# GATEWAY.net
KiCad netlist of a schematic drawn in Altium Designer
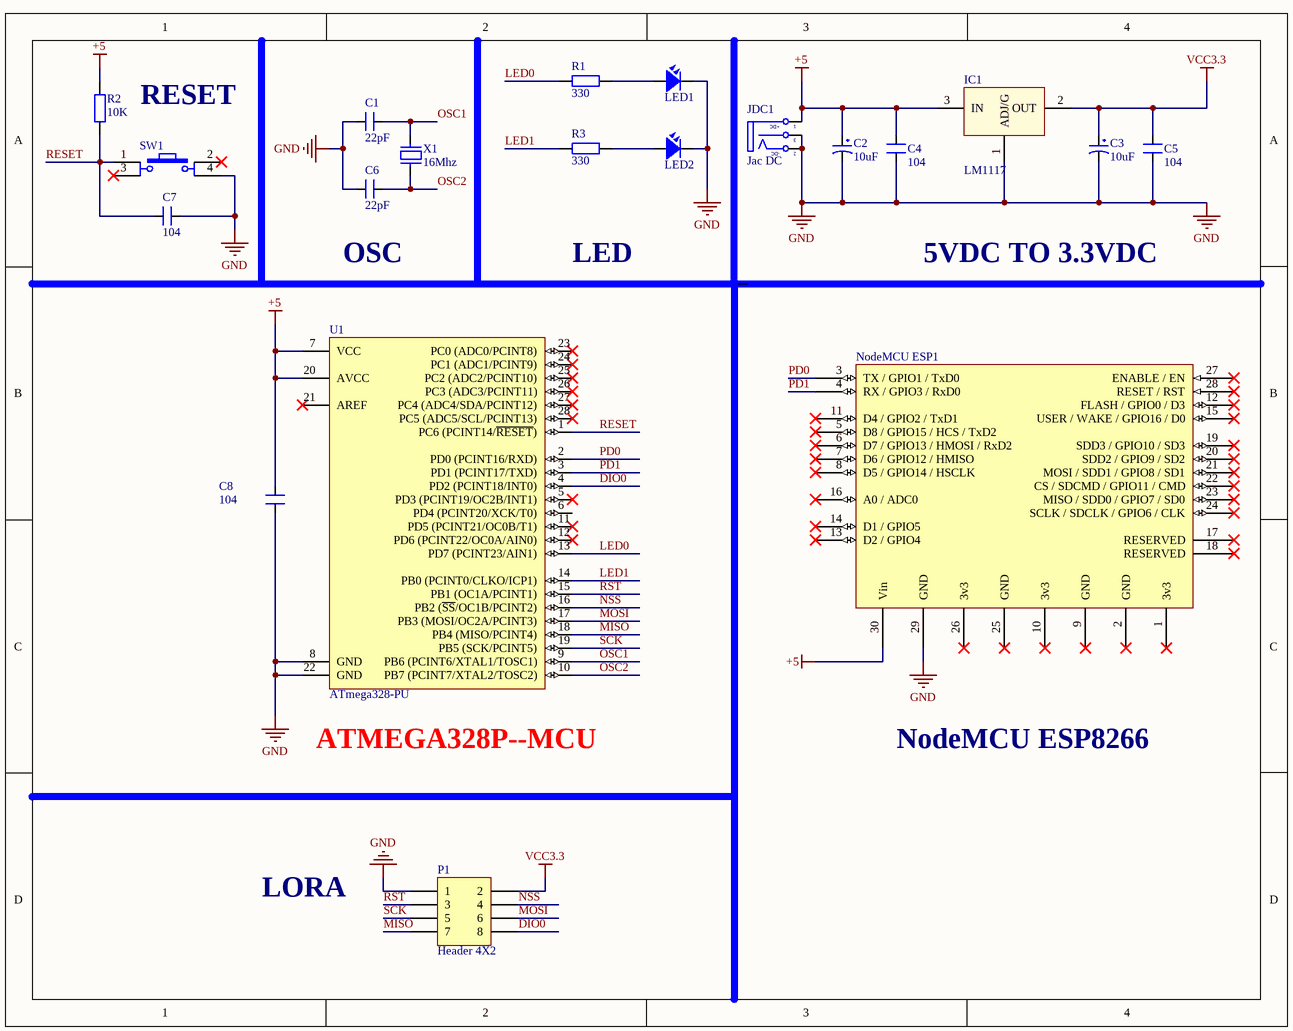
[diagram p0: GATEWAY.SchDoc]

(export (version "E")
  (design (tool "Eeschema 10.0.6"))
  (components
    (comp (ref "C1")
      (value "22pF")
      (footprint "CN1")
      (description "Cap np  1pF - 472pF")
      (libsource (lib "syhaunguyen") (part "CN1"))
    )
    (comp (ref "C2")
      (value "10uF")
      (footprint "CP1/2")
      (description "Cap P  0,1uF < 22uF , 16 - 50V")
      (libsource (lib "My Library") (part "CP1"))
    )
    (comp (ref "C3")
      (value "10uF")
      (footprint "CP1/2")
      (description "Cap P  0,1uF < 22uF , 16 - 50V")
      (libsource (lib "My Library") (part "CP1"))
    )
    (comp (ref "C4")
      (value "104")
      (footprint "CN2")
      (description "Cap np 104 => 105pF")
      (libsource (lib "syhaunguyen") (part "CN2"))
    )
    (comp (ref "C5")
      (value "104")
      (footprint "CN2")
      (description "Cap np 104 => 105pF")
      (libsource (lib "syhaunguyen") (part "CN2"))
    )
    (comp (ref "C6")
      (value "22pF")
      (footprint "CN1")
      (description "Cap np  1pF - 472pF")
      (libsource (lib "syhaunguyen") (part "CN1"))
    )
    (comp (ref "C7")
      (value "104")
      (footprint "CN2")
      (description "Cap np 104 => 105pF")
      (libsource (lib "syhaunguyen") (part "CN2"))
    )
    (comp (ref "C8")
      (value "104")
      (footprint "CN2")
      (description "Cap np 104 => 105pF")
      (libsource (lib "syhaunguyen") (part "CN2"))
    )
    (comp (ref "IC1")
      (value "LM1117")
      (footprint "SOT223-4N")
      (description "Available in 1.8V, 2.5V, 2.85V, 3.3V, 5V, and  Adjustable Versions")
      (libsource (lib "syhaunguyen") (part "LM1117"))
    )
    (comp (ref "JDC1")
      (value "Jac DC")
      (footprint "DC0")
      (description "Jac DC input")
      (libsource (lib "LIBRARY1") (part "DCIN"))
    )
    (comp (ref "LED1")
      (value "LED")
      (footprint "LED-5-Yellow")
      (description "LED Single colour Green and Red")
      (libsource (lib "syhaunguyen") (part "LED"))
    )
    (comp (ref "LED2")
      (value "LED")
      (footprint "LED-5-BLUE")
      (description "LED Single colour Green and Red")
      (libsource (lib "syhaunguyen") (part "LED"))
    )
    (comp (ref "NodeMCU ESP1")
      (value "NodeMCU")
      (footprint "NodeMCU DevKit v1.0 - Inside Labels")
      (libsource (lib "NodeMCU") (part "NodeMCU DevKit v1.0"))
    )
    (comp (ref "P1")
      (value "Header 4X2")
      (footprint "HDR2X4")
      (description "Header, 4-Pin, Dual row")
      (fields (field (name "PUBLISHER") "Altium Limited"))
      (libsource (lib "My Library") (part "Header 4X2"))
    )
    (comp (ref "R1")
      (value "330")
      (footprint "R1/2W")
      (description "Resistor 1/4W")
      (libsource (lib "syhaunguyen") (part "R1/4W"))
    )
    (comp (ref "R2")
      (value "10K")
      (footprint "R1/2W")
      (description "Resistor 1/4W")
      (libsource (lib "syhaunguyen") (part "R1/4W"))
    )
    (comp (ref "R3")
      (value "330")
      (footprint "R1/2W")
      (description "Resistor 1/4W")
      (libsource (lib "syhaunguyen") (part "R1/4W"))
    )
    (comp (ref "SW1")
      (value "SW")
      (footprint "SW4")
      (description "Switch button 4 pin")
      (libsource (lib "syhaunguyen") (part "SW4"))
    )
    (comp (ref "U1")
      (value "ATmega328-PU")
      (footprint "DIP28")
      (fields (field (name "PUBLISHER") "Altium Limited"))
      (libsource (lib "LIBRARY1") (part "ATmega328-PU"))
    )
    (comp (ref "X1")
      (value "16Mhz")
      (footprint "XT2")
      (description "Crystal For all Crystal 2pin.")
      (libsource (lib "hphonglib") (part "XT2"))
    )
  )
  (nets
    (net (code "1") (name "+5") (class "Default")
      (node (ref "C2") (pin "1") (pinfunction "1_1") (pintype "passive"))
      (node (ref "C4") (pin "2") (pinfunction "2_2") (pintype "passive"))
      (node (ref "C8") (pin "2") (pinfunction "2_2") (pintype "passive"))
      (node (ref "IC1") (pin "3") (pinfunction "IN_3") (pintype "passive"))
      (node (ref "JDC1") (pin "1") (pinfunction "T_1") (pintype "passive"))
      (node (ref "NodeMCU ESP1") (pin "30") (pinfunction "Vin_30") (pintype "passive"))
      (node (ref "R2") (pin "2") (pinfunction "2_2") (pintype "passive"))
      (node (ref "U1") (pin "20") (pinfunction "AVCC_20") (pintype "power_in"))
      (node (ref "U1") (pin "7") (pinfunction "VCC_7") (pintype "power_in"))
    )
    (net (code "2") (name "/DIO0") (class "Default")
      (node (ref "P1") (pin "8") (pinfunction "8_8") (pintype "passive"))
      (node (ref "U1") (pin "4") (pinfunction "PD2_(PCINT18/INT0)_4") (pintype "bidirectional"))
    )
    (net (code "3") (name "/LED0") (class "Default")
      (node (ref "R1") (pin "2") (pinfunction "2_2") (pintype "passive"))
      (node (ref "U1") (pin "13") (pinfunction "PD7_(PCINT23/AIN1)_13") (pintype "bidirectional"))
    )
    (net (code "4") (name "/LED1") (class "Default")
      (node (ref "R3") (pin "2") (pinfunction "2_2") (pintype "passive"))
      (node (ref "U1") (pin "14") (pinfunction "PB0_(PCINT0/CLKO/ICP1)_14") (pintype "bidirectional"))
    )
    (net (code "5") (name "/MISO") (class "Default")
      (node (ref "P1") (pin "7") (pinfunction "7_7") (pintype "passive"))
      (node (ref "U1") (pin "18") (pinfunction "PB4_(MISO/PCINT4)_18") (pintype "bidirectional"))
    )
    (net (code "6") (name "/MOSI") (class "Default")
      (node (ref "P1") (pin "6") (pinfunction "6_6") (pintype "passive"))
      (node (ref "U1") (pin "17") (pinfunction "PB3_(MOSI/OC2A/PCINT3)_17") (pintype "bidirectional"))
    )
    (net (code "7") (name "/NSS") (class "Default")
      (node (ref "P1") (pin "4") (pinfunction "4_4") (pintype "passive"))
      (node (ref "U1") (pin "16") (pinfunction "PB2_(~{SS}/OC1B/PCINT2)_16") (pintype "bidirectional"))
    )
    (net (code "8") (name "/OSC1") (class "Default")
      (node (ref "C1") (pin "2") (pinfunction "2_2") (pintype "passive"))
      (node (ref "U1") (pin "9") (pinfunction "PB6_(PCINT6/XTAL1/TOSC1)_9") (pintype "bidirectional"))
      (node (ref "X1") (pin "2") (pinfunction "2_2") (pintype "passive"))
    )
    (net (code "9") (name "/OSC2") (class "Default")
      (node (ref "C6") (pin "2") (pinfunction "2_2") (pintype "passive"))
      (node (ref "U1") (pin "10") (pinfunction "PB7_(PCINT7/XTAL2/TOSC2)_10") (pintype "bidirectional"))
      (node (ref "X1") (pin "1") (pinfunction "1_1") (pintype "passive"))
    )
    (net (code "10") (name "/PD0") (class "Default")
      (node (ref "NodeMCU ESP1") (pin "3") (pinfunction "TX_/_GPIO1_/_TxD0_3") (pintype "bidirectional"))
      (node (ref "U1") (pin "2") (pinfunction "PD0_(PCINT16/RXD)_2") (pintype "bidirectional"))
    )
    (net (code "11") (name "/PD1") (class "Default")
      (node (ref "NodeMCU ESP1") (pin "4") (pinfunction "RX_/_GPIO3_/_RxD0_4") (pintype "bidirectional"))
      (node (ref "U1") (pin "3") (pinfunction "PD1_(PCINT17/TXD)_3") (pintype "bidirectional"))
    )
    (net (code "12") (name "/RESET") (class "Default")
      (node (ref "C7") (pin "1") (pinfunction "1_1") (pintype "passive"))
      (node (ref "R2") (pin "1") (pinfunction "1_1") (pintype "passive"))
      (node (ref "SW1") (pin "1") (pintype "passive"))
      (node (ref "U1") (pin "1") (pinfunction "PC6_(PCINT14/~{RESET})_1") (pintype "bidirectional"))
    )
    (net (code "13") (name "/RST") (class "Default")
      (node (ref "P1") (pin "3") (pinfunction "3_3") (pintype "passive"))
      (node (ref "U1") (pin "15") (pinfunction "PB1_(OC1A/PCINT1)_15") (pintype "bidirectional"))
    )
    (net (code "14") (name "/SCK") (class "Default")
      (node (ref "P1") (pin "5") (pinfunction "5_5") (pintype "passive"))
      (node (ref "U1") (pin "19") (pinfunction "PB5_(SCK/PCINT5)_19") (pintype "bidirectional"))
    )
    (net (code "15") (name "GND") (class "Default")
      (node (ref "C1") (pin "1") (pinfunction "1_1") (pintype "passive"))
      (node (ref "C2") (pin "2") (pinfunction "2_2") (pintype "passive"))
      (node (ref "C3") (pin "2") (pinfunction "2_2") (pintype "passive"))
      (node (ref "C4") (pin "1") (pinfunction "1_1") (pintype "passive"))
      (node (ref "C5") (pin "1") (pinfunction "1_1") (pintype "passive"))
      (node (ref "C6") (pin "1") (pinfunction "1_1") (pintype "passive"))
      (node (ref "C7") (pin "2") (pinfunction "2_2") (pintype "passive"))
      (node (ref "C8") (pin "1") (pinfunction "1_1") (pintype "passive"))
      (node (ref "IC1") (pin "1") (pinfunction "ADJ/G_1") (pintype "passive"))
      (node (ref "JDC1") (pin "2") (pinfunction "TN_2") (pintype "passive"))
      (node (ref "JDC1") (pin "3") (pinfunction "S_3") (pintype "power_in"))
      (node (ref "LED1") (pin "2") (pinfunction "2_2") (pintype "passive"))
      (node (ref "LED2") (pin "2") (pinfunction "2_2") (pintype "passive"))
      (node (ref "NodeMCU ESP1") (pin "29") (pinfunction "GND_29") (pintype "passive"))
      (node (ref "P1") (pin "1") (pinfunction "1_1") (pintype "passive"))
      (node (ref "SW1") (pin "4") (pintype "passive"))
      (node (ref "U1") (pin "22") (pinfunction "GND_22") (pintype "power_in"))
      (node (ref "U1") (pin "8") (pinfunction "GND_8") (pintype "power_in"))
    )
    (net (code "16") (name "Net-(LED1-Pad1)") (class "Default")
      (node (ref "LED1") (pin "1") (pinfunction "1_1") (pintype "passive"))
      (node (ref "R1") (pin "1") (pinfunction "1_1") (pintype "passive"))
    )
    (net (code "17") (name "Net-(LED2-Pad1)") (class "Default")
      (node (ref "LED2") (pin "1") (pinfunction "1_1") (pintype "passive"))
      (node (ref "R3") (pin "1") (pinfunction "1_1") (pintype "passive"))
    )
    (net (code "18") (name "VCC3.3") (class "Default")
      (node (ref "C3") (pin "1") (pinfunction "1_1") (pintype "passive"))
      (node (ref "C5") (pin "2") (pinfunction "2_2") (pintype "passive"))
      (node (ref "IC1") (pin "2") (pinfunction "OUT_2") (pintype "passive"))
      (node (ref "P1") (pin "2") (pinfunction "2_2") (pintype "passive"))
    )
    (net (code "19") (name "unconnected-(NodeMCU ESP1-3v3-Pad1)") (class "Default")
      (node (ref "NodeMCU ESP1") (pin "1") (pinfunction "3v3_1") (pintype "power_in+no_connect"))
    )
    (net (code "20") (name "unconnected-(NodeMCU ESP1-3v3-Pad10)") (class "Default")
      (node (ref "NodeMCU ESP1") (pin "10") (pinfunction "3v3_10") (pintype "power_in+no_connect"))
    )
    (net (code "21") (name "unconnected-(NodeMCU ESP1-3v3-Pad26)") (class "Default")
      (node (ref "NodeMCU ESP1") (pin "26") (pinfunction "3v3_26") (pintype "power_in+no_connect"))
    )
    (net (code "22") (name "unconnected-(NodeMCU ESP1-A0_{slash}_ADC0-Pad16)") (class "Default")
      (node (ref "NodeMCU ESP1") (pin "16") (pinfunction "A0_/_ADC0_16") (pintype "bidirectional+no_connect"))
    )
    (net (code "23") (name "unconnected-(NodeMCU ESP1-CS_{slash}_SDCMD_{slash}_GPIO11_{slash}_CMD-Pad22)") (class "Default")
      (node (ref "NodeMCU ESP1") (pin "22") (pinfunction "CS_/_SDCMD_/_GPIO11_/_CMD_22") (pintype "bidirectional+no_connect"))
    )
    (net (code "24") (name "unconnected-(NodeMCU ESP1-D1_{slash}_GPIO5-Pad14)") (class "Default")
      (node (ref "NodeMCU ESP1") (pin "14") (pinfunction "D1_/_GPIO5_14") (pintype "bidirectional+no_connect"))
    )
    (net (code "25") (name "unconnected-(NodeMCU ESP1-D2_{slash}_GPIO4-Pad13)") (class "Default")
      (node (ref "NodeMCU ESP1") (pin "13") (pinfunction "D2_/_GPIO4_13") (pintype "bidirectional+no_connect"))
    )
    (net (code "26") (name "unconnected-(NodeMCU ESP1-D4_{slash}_GPIO2_{slash}_TxD1-Pad11)") (class "Default")
      (node (ref "NodeMCU ESP1") (pin "11") (pinfunction "D4_/_GPIO2_/_TxD1_11") (pintype "bidirectional+no_connect"))
    )
    (net (code "27") (name "unconnected-(NodeMCU ESP1-D5_{slash}_GPIO14_{slash}_HSCLK-Pad8)") (class "Default")
      (node (ref "NodeMCU ESP1") (pin "8") (pinfunction "D5_/_GPIO14_/_HSCLK_8") (pintype "bidirectional+no_connect"))
    )
    (net (code "28") (name "unconnected-(NodeMCU ESP1-D6_{slash}_GPIO12_{slash}_HMISO-Pad7)") (class "Default")
      (node (ref "NodeMCU ESP1") (pin "7") (pinfunction "D6_/_GPIO12_/_HMISO_7") (pintype "bidirectional+no_connect"))
    )
    (net (code "29") (name "unconnected-(NodeMCU ESP1-D7_{slash}_GPIO13_{slash}_HMOSI_{slash}_RxD2-Pad6)") (class "Default")
      (node (ref "NodeMCU ESP1") (pin "6") (pinfunction "D7_/_GPIO13_/_HMOSI_/_RxD2_6") (pintype "bidirectional+no_connect"))
    )
    (net (code "30") (name "unconnected-(NodeMCU ESP1-D8_{slash}_GPIO15_{slash}_HCS_{slash}_TxD2-Pad5)") (class "Default")
      (node (ref "NodeMCU ESP1") (pin "5") (pinfunction "D8_/_GPIO15_/_HCS_/_TxD2_5") (pintype "bidirectional+no_connect"))
    )
    (net (code "31") (name "unconnected-(NodeMCU ESP1-ENABLE_{slash}_EN-Pad27)") (class "Default")
      (node (ref "NodeMCU ESP1") (pin "27") (pinfunction "ENABLE_/_EN_27") (pintype "input+no_connect"))
    )
    (net (code "32") (name "unconnected-(NodeMCU ESP1-FLASH_{slash}_GPIO0_{slash}_D3-Pad12)") (class "Default")
      (node (ref "NodeMCU ESP1") (pin "12") (pinfunction "FLASH_/_GPIO0_/_D3_12") (pintype "bidirectional+no_connect"))
    )
    (net (code "33") (name "unconnected-(NodeMCU ESP1-GND-Pad2)") (class "Default")
      (node (ref "NodeMCU ESP1") (pin "2") (pinfunction "GND_2") (pintype "power_in+no_connect"))
    )
    (net (code "34") (name "unconnected-(NodeMCU ESP1-GND-Pad9)") (class "Default")
      (node (ref "NodeMCU ESP1") (pin "9") (pinfunction "GND_9") (pintype "power_in+no_connect"))
    )
    (net (code "35") (name "unconnected-(NodeMCU ESP1-GND-Pad25)") (class "Default")
      (node (ref "NodeMCU ESP1") (pin "25") (pinfunction "GND_25") (pintype "power_in+no_connect"))
    )
    (net (code "36") (name "unconnected-(NodeMCU ESP1-MISO_{slash}_SDD0_{slash}_GPIO7_{slash}_SD0-Pad23)") (class "Default")
      (node (ref "NodeMCU ESP1") (pin "23") (pinfunction "MISO_/_SDD0_/_GPIO7_/_SD0_23") (pintype "bidirectional+no_connect"))
    )
    (net (code "37") (name "unconnected-(NodeMCU ESP1-MOSI_{slash}_SDD1_{slash}_GPIO8_{slash}_SD1-Pad21)") (class "Default")
      (node (ref "NodeMCU ESP1") (pin "21") (pinfunction "MOSI_/_SDD1_/_GPIO8_/_SD1_21") (pintype "bidirectional+no_connect"))
    )
    (net (code "38") (name "unconnected-(NodeMCU ESP1-RESERVED-Pad17)") (class "Default")
      (node (ref "NodeMCU ESP1") (pin "17") (pinfunction "RESERVED_17") (pintype "passive+no_connect"))
    )
    (net (code "39") (name "unconnected-(NodeMCU ESP1-RESERVED-Pad18)") (class "Default")
      (node (ref "NodeMCU ESP1") (pin "18") (pinfunction "RESERVED_18") (pintype "passive+no_connect"))
    )
    (net (code "40") (name "unconnected-(NodeMCU ESP1-RESET_{slash}_RST-Pad28)") (class "Default")
      (node (ref "NodeMCU ESP1") (pin "28") (pinfunction "RESET_/_RST_28") (pintype "input+no_connect"))
    )
    (net (code "41") (name "unconnected-(NodeMCU ESP1-SCLK_{slash}_SDCLK_{slash}_GPIO6_{slash}_CLK-Pad24)") (class "Default")
      (node (ref "NodeMCU ESP1") (pin "24") (pinfunction "SCLK_/_SDCLK_/_GPIO6_/_CLK_24") (pintype "bidirectional+no_connect"))
    )
    (net (code "42") (name "unconnected-(NodeMCU ESP1-SDD2_{slash}_GPIO9_{slash}_SD2-Pad20)") (class "Default")
      (node (ref "NodeMCU ESP1") (pin "20") (pinfunction "SDD2_/_GPIO9_/_SD2_20") (pintype "bidirectional+no_connect"))
    )
    (net (code "43") (name "unconnected-(NodeMCU ESP1-SDD3_{slash}_GPIO10_{slash}_SD3-Pad19)") (class "Default")
      (node (ref "NodeMCU ESP1") (pin "19") (pinfunction "SDD3_/_GPIO10_/_SD3_19") (pintype "bidirectional+no_connect"))
    )
    (net (code "44") (name "unconnected-(NodeMCU ESP1-USER_{slash}_WAKE_{slash}_GPIO16_{slash}_D0-Pad15)") (class "Default")
      (node (ref "NodeMCU ESP1") (pin "15") (pinfunction "USER_/_WAKE_/_GPIO16_/_D0_15") (pintype "bidirectional+no_connect"))
    )
    (net (code "45") (name "unconnected-(SW1-Pad2)") (class "Default")
      (node (ref "SW1") (pin "2") (pintype "passive+no_connect"))
    )
    (net (code "46") (name "unconnected-(SW1-Pad3)") (class "Default")
      (node (ref "SW1") (pin "3") (pintype "passive+no_connect"))
    )
    (net (code "47") (name "unconnected-(U1-AREF-Pad21)") (class "Default")
      (node (ref "U1") (pin "21") (pinfunction "AREF_21") (pintype "power_in+no_connect"))
    )
    (net (code "48") (name "unconnected-(U1-PC0_(ADC0{slash}PCINT8)-Pad23)") (class "Default")
      (node (ref "U1") (pin "23") (pinfunction "PC0_(ADC0/PCINT8)_23") (pintype "bidirectional+no_connect"))
    )
    (net (code "49") (name "unconnected-(U1-PC1_(ADC1{slash}PCINT9)-Pad24)") (class "Default")
      (node (ref "U1") (pin "24") (pinfunction "PC1_(ADC1/PCINT9)_24") (pintype "bidirectional+no_connect"))
    )
    (net (code "50") (name "unconnected-(U1-PC2_(ADC2{slash}PCINT10)-Pad25)") (class "Default")
      (node (ref "U1") (pin "25") (pinfunction "PC2_(ADC2/PCINT10)_25") (pintype "bidirectional+no_connect"))
    )
    (net (code "51") (name "unconnected-(U1-PC3_(ADC3{slash}PCINT11)-Pad26)") (class "Default")
      (node (ref "U1") (pin "26") (pinfunction "PC3_(ADC3/PCINT11)_26") (pintype "bidirectional+no_connect"))
    )
    (net (code "52") (name "unconnected-(U1-PC4_(ADC4{slash}SDA{slash}PCINT12)-Pad27)") (class "Default")
      (node (ref "U1") (pin "27") (pinfunction "PC4_(ADC4/SDA/PCINT12)_27") (pintype "bidirectional+no_connect"))
    )
    (net (code "53") (name "unconnected-(U1-PC5_(ADC5{slash}SCL{slash}PCINT13)-Pad28)") (class "Default")
      (node (ref "U1") (pin "28") (pinfunction "PC5_(ADC5/SCL/PCINT13)_28") (pintype "bidirectional+no_connect"))
    )
    (net (code "54") (name "unconnected-(U1-PD3_(PCINT19{slash}OC2B{slash}INT1)-Pad5)") (class "Default")
      (node (ref "U1") (pin "5") (pinfunction "PD3_(PCINT19/OC2B/INT1)_5") (pintype "bidirectional+no_connect"))
    )
    (net (code "55") (name "unconnected-(U1-PD4_(PCINT20{slash}XCK{slash}T0)-Pad6)") (class "Default")
      (node (ref "U1") (pin "6") (pinfunction "PD4_(PCINT20/XCK/T0)_6") (pintype "bidirectional"))
    )
    (net (code "56") (name "unconnected-(U1-PD5_(PCINT21{slash}OC0B{slash}T1)-Pad11)") (class "Default")
      (node (ref "U1") (pin "11") (pinfunction "PD5_(PCINT21/OC0B/T1)_11") (pintype "bidirectional+no_connect"))
    )
    (net (code "57") (name "unconnected-(U1-PD6_(PCINT22{slash}OC0A{slash}AIN0)-Pad12)") (class "Default")
      (node (ref "U1") (pin "12") (pinfunction "PD6_(PCINT22/OC0A/AIN0)_12") (pintype "bidirectional+no_connect"))
    )
  )
)
